# schematic.net
KiCad netlist of a schematic drawn in EAGLE
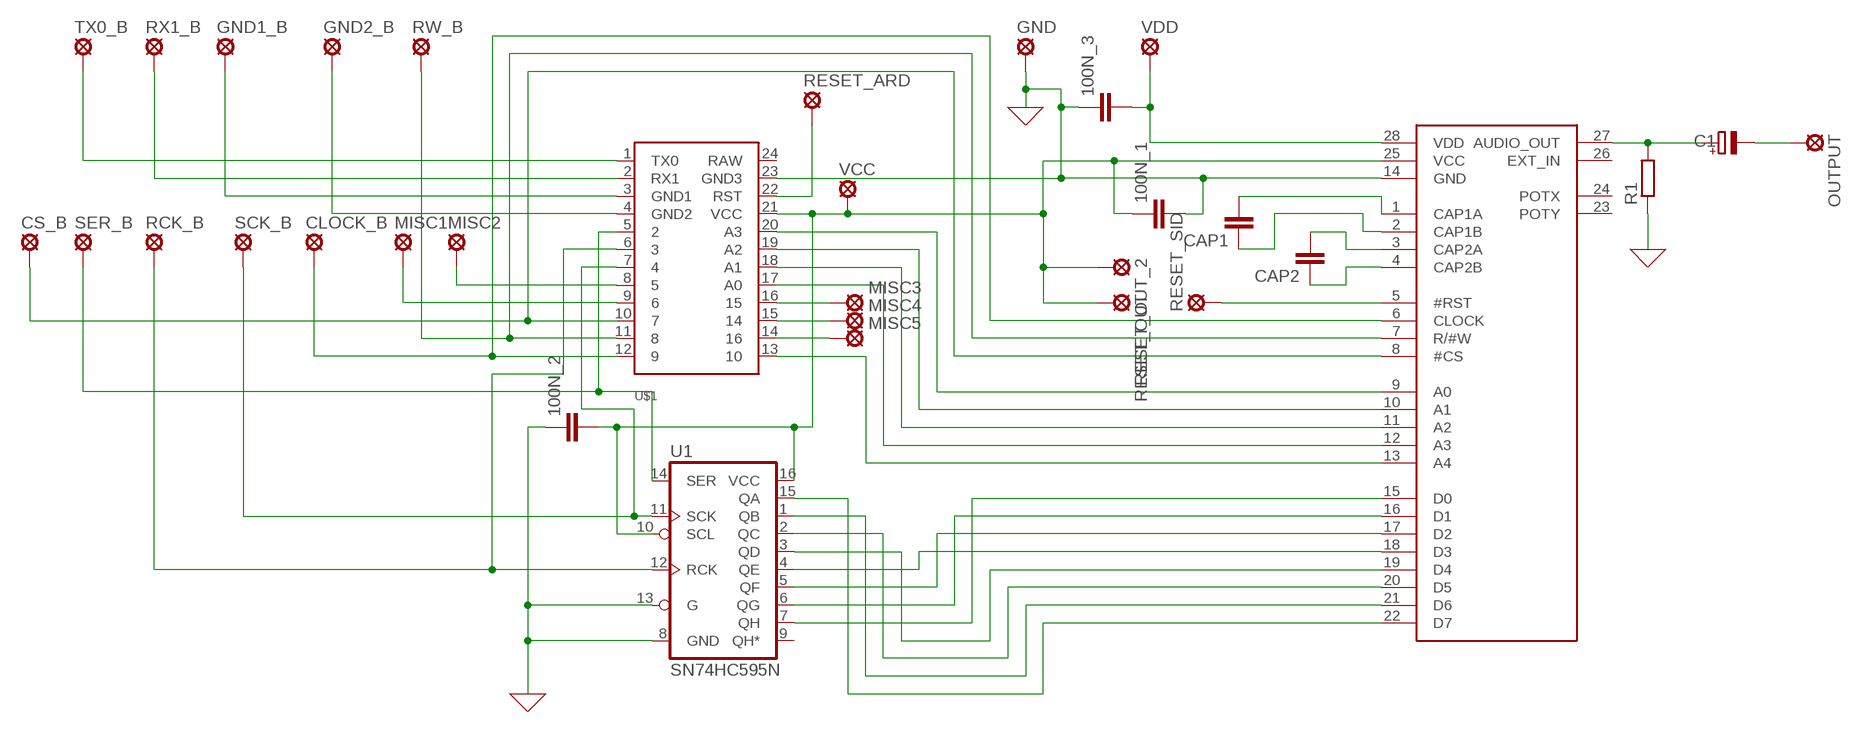
[diagram p0: schematic, sheet 1]

(export (version "E")
  (design (tool "Eeschema 10.0.6"))
  (components
    (comp (ref "100N_1")
      (value "C-EU025-025X050")
      (footprint "eagle-import:C025-025X050")
      (libsource (lib "eagle-import") (part "C-EU025-025X050"))
    )
    (comp (ref "100N_2")
      (value "C-EU050-025X075")
      (footprint "eagle-import:C050-025X075")
      (libsource (lib "eagle-import") (part "C-EU050-025X075"))
    )
    (comp (ref "100N_3")
      (value "C-EU050-025X075")
      (footprint "eagle-import:C050-025X075")
      (libsource (lib "eagle-import") (part "C-EU050-025X075"))
    )
    (comp (ref "C1")
      (value "CPOL-EUE2.5-5")
      (footprint "eagle-import:E2,5-5")
      (libsource (lib "eagle-import") (part "CPOL-EUE2.5-5"))
    )
    (comp (ref "CAP1")
      (value "C-EU050-025X075")
      (footprint "eagle-import:C050-025X075")
      (libsource (lib "eagle-import") (part "C-EU050-025X075"))
    )
    (comp (ref "CAP2")
      (value "C-EU050-025X075")
      (footprint "eagle-import:C050-025X075")
      (libsource (lib "eagle-import") (part "C-EU050-025X075"))
    )
    (comp (ref "CLOCK_B")
      (value "LSP11")
      (footprint "eagle-import:LSP11")
      (libsource (lib "eagle-import") (part "LSP11"))
    )
    (comp (ref "CS_B")
      (value "LSP11")
      (footprint "eagle-import:LSP11")
      (libsource (lib "eagle-import") (part "LSP11"))
    )
    (comp (ref "GND")
      (value "LSP11")
      (footprint "eagle-import:LSP11")
      (libsource (lib "eagle-import") (part "LSP11"))
    )
    (comp (ref "GND1_B")
      (value "LSP11")
      (footprint "eagle-import:LSP11")
      (libsource (lib "eagle-import") (part "LSP11"))
    )
    (comp (ref "GND2_B")
      (value "LSP11")
      (footprint "eagle-import:LSP11")
      (libsource (lib "eagle-import") (part "LSP11"))
    )
    (comp (ref "MISC1")
      (value "LSP11")
      (footprint "eagle-import:LSP11")
      (libsource (lib "eagle-import") (part "LSP11"))
    )
    (comp (ref "MISC2")
      (value "LSP11")
      (footprint "eagle-import:LSP11")
      (libsource (lib "eagle-import") (part "LSP11"))
    )
    (comp (ref "MISC3")
      (value "LSP11")
      (footprint "eagle-import:LSP11")
      (libsource (lib "eagle-import") (part "LSP11"))
    )
    (comp (ref "MISC4")
      (value "LSP11")
      (footprint "eagle-import:LSP11")
      (libsource (lib "eagle-import") (part "LSP11"))
    )
    (comp (ref "MISC5")
      (value "LSP11")
      (footprint "eagle-import:LSP11")
      (libsource (lib "eagle-import") (part "LSP11"))
    )
    (comp (ref "OUTPUT")
      (value "LSP11")
      (footprint "eagle-import:LSP11")
      (libsource (lib "eagle-import") (part "LSP11"))
    )
    (comp (ref "R1")
      (value "R-EU_0204/7")
      (footprint "eagle-import:0204_7")
      (libsource (lib "eagle-import") (part "R-EU_0204/7"))
    )
    (comp (ref "RCK_B")
      (value "LSP11")
      (footprint "eagle-import:LSP11")
      (libsource (lib "eagle-import") (part "LSP11"))
    )
    (comp (ref "RESET_ARD")
      (value "LSP11")
      (footprint "eagle-import:LSP11")
      (libsource (lib "eagle-import") (part "LSP11"))
    )
    (comp (ref "RESET_OUT")
      (value "LSP11")
      (footprint "eagle-import:LSP11")
      (libsource (lib "eagle-import") (part "LSP11"))
    )
    (comp (ref "RESET_OUT_2")
      (value "LSP11")
      (footprint "eagle-import:LSP11")
      (libsource (lib "eagle-import") (part "LSP11"))
    )
    (comp (ref "RESET_SID")
      (value "LSP11")
      (footprint "eagle-import:LSP11")
      (libsource (lib "eagle-import") (part "LSP11"))
    )
    (comp (ref "RW_B")
      (value "LSP11")
      (footprint "eagle-import:LSP11")
      (libsource (lib "eagle-import") (part "LSP11"))
    )
    (comp (ref "RX1_B")
      (value "LSP11")
      (footprint "eagle-import:LSP11")
      (libsource (lib "eagle-import") (part "LSP11"))
    )
    (comp (ref "SCK_B")
      (value "LSP11")
      (footprint "eagle-import:LSP11")
      (libsource (lib "eagle-import") (part "LSP11"))
    )
    (comp (ref "SER_B")
      (value "LSP11")
      (footprint "eagle-import:LSP11")
      (libsource (lib "eagle-import") (part "LSP11"))
    )
    (comp (ref "TX0_B")
      (value "LSP11")
      (footprint "eagle-import:LSP11")
      (libsource (lib "eagle-import") (part "LSP11"))
    )
    (comp (ref "U$1")
      (value "ARDUINOPROMICRO1")
      (footprint "eagle-import:PROMICRO")
      (libsource (lib "eagle-import") (part "ARDUINOPROMICRO1"))
    )
    (comp (ref "U$2")
      (value "SID_6581")
      (footprint "eagle-import:DIL28-6")
      (libsource (lib "eagle-import") (part "SID_6581"))
    )
    (comp (ref "U1")
      (value "SN74HC595N")
      (footprint "eagle-import:DIP16")
      (libsource (lib "eagle-import") (part "74595NHC"))
    )
    (comp (ref "VCC")
      (value "LSP11")
      (footprint "eagle-import:LSP11")
      (libsource (lib "eagle-import") (part "LSP11"))
    )
    (comp (ref "VDD")
      (value "LSP11")
      (footprint "eagle-import:LSP11")
      (libsource (lib "eagle-import") (part "LSP11"))
    )
  )
  (nets
    (net (code "1") (name "GND") (class "Default")
      (node (ref "100N_1") (pin "2") (pinfunction "2_2") (pintype "passive"))
      (node (ref "100N_2") (pin "1") (pinfunction "1_1") (pintype "passive"))
      (node (ref "100N_3") (pin "1") (pinfunction "1_1") (pintype "passive"))
      (node (ref "GND") (pin "MP") (pinfunction "MP_MP") (pintype "passive"))
      (node (ref "R1") (pin "1") (pinfunction "1_1") (pintype "passive"))
      (node (ref "U$1") (pin "23") (pinfunction "GND3_23") (pintype "bidirectional"))
      (node (ref "U$2") (pin "14") (pinfunction "GND_14") (pintype "bidirectional"))
      (node (ref "U1") (pin "13") (pinfunction "G_13") (pintype "input"))
      (node (ref "U1") (pin "8") (pinfunction "GND_8") (pintype "power_in"))
    )
    (net (code "2") (name "Net-(C1-Pad-)") (class "Default")
      (node (ref "C1") (pin "-") (pinfunction "-_-") (pintype "passive"))
      (node (ref "OUTPUT") (pin "MP") (pinfunction "MP_MP") (pintype "passive"))
    )
    (net (code "3") (name "Net-(U$1-2)") (class "Default")
      (node (ref "SER_B") (pin "MP") (pinfunction "MP_MP") (pintype "passive"))
      (node (ref "U$1") (pin "5") (pinfunction "2_5") (pintype "bidirectional"))
      (node (ref "U1") (pin "14") (pinfunction "SER_14") (pintype "input"))
    )
    (net (code "4") (name "Net-(U$1-3)") (class "Default")
      (node (ref "RCK_B") (pin "MP") (pinfunction "MP_MP") (pintype "passive"))
      (node (ref "U$1") (pin "6") (pinfunction "3_6") (pintype "bidirectional"))
      (node (ref "U1") (pin "12") (pinfunction "RCK_12") (pintype "input"))
    )
    (net (code "5") (name "Net-(U$1-4)") (class "Default")
      (node (ref "SCK_B") (pin "MP") (pinfunction "MP_MP") (pintype "passive"))
      (node (ref "U$1") (pin "7") (pinfunction "4_7") (pintype "bidirectional"))
      (node (ref "U1") (pin "11") (pinfunction "SCK_11") (pintype "input"))
    )
    (net (code "6") (name "Net-(U$1-5)") (class "Default")
      (node (ref "MISC2") (pin "MP") (pinfunction "MP_MP") (pintype "passive"))
      (node (ref "U$1") (pin "8") (pinfunction "5_8") (pintype "bidirectional"))
    )
    (net (code "7") (name "Net-(U$1-6)") (class "Default")
      (node (ref "MISC1") (pin "MP") (pinfunction "MP_MP") (pintype "passive"))
      (node (ref "U$1") (pin "9") (pinfunction "6_9") (pintype "bidirectional"))
    )
    (net (code "8") (name "Net-(U$1-7)") (class "Default")
      (node (ref "CS_B") (pin "MP") (pinfunction "MP_MP") (pintype "passive"))
      (node (ref "U$1") (pin "10") (pinfunction "7_10") (pintype "bidirectional"))
      (node (ref "U$2") (pin "8") (pinfunction "#CS_8") (pintype "bidirectional"))
    )
    (net (code "9") (name "Net-(U$1-8)") (class "Default")
      (node (ref "RW_B") (pin "MP") (pinfunction "MP_MP") (pintype "passive"))
      (node (ref "U$1") (pin "11") (pinfunction "8_11") (pintype "bidirectional"))
      (node (ref "U$2") (pin "7") (pinfunction "R/#W_7") (pintype "bidirectional"))
    )
    (net (code "10") (name "Net-(U$1-9)") (class "Default")
      (node (ref "CLOCK_B") (pin "MP") (pinfunction "MP_MP") (pintype "passive"))
      (node (ref "U$1") (pin "12") (pinfunction "9_12") (pintype "bidirectional"))
      (node (ref "U$2") (pin "6") (pinfunction "CLOCK_6") (pintype "bidirectional"))
    )
    (net (code "11") (name "Net-(U$1-10)") (class "Default")
      (node (ref "U$1") (pin "13") (pinfunction "10_13") (pintype "bidirectional"))
      (node (ref "U$2") (pin "13") (pinfunction "A4_13") (pintype "bidirectional"))
    )
    (net (code "12") (name "Net-(U$1-14)") (class "Default")
      (node (ref "MISC4") (pin "MP") (pinfunction "MP_MP") (pintype "passive"))
      (node (ref "U$1") (pin "15") (pinfunction "14_15") (pintype "bidirectional"))
    )
    (net (code "13") (name "Net-(U$1-15)") (class "Default")
      (node (ref "MISC3") (pin "MP") (pinfunction "MP_MP") (pintype "passive"))
      (node (ref "U$1") (pin "16") (pinfunction "15_16") (pintype "bidirectional"))
    )
    (net (code "14") (name "Net-(U$1-16)") (class "Default")
      (node (ref "MISC5") (pin "MP") (pinfunction "MP_MP") (pintype "passive"))
      (node (ref "U$1") (pin "14") (pinfunction "16_14") (pintype "bidirectional"))
    )
    (net (code "15") (name "Net-(U$1-A0)") (class "Default")
      (node (ref "U$1") (pin "17") (pinfunction "A0_17") (pintype "bidirectional"))
      (node (ref "U$2") (pin "12") (pinfunction "A3_12") (pintype "bidirectional"))
    )
    (net (code "16") (name "Net-(U$1-A1)") (class "Default")
      (node (ref "U$1") (pin "18") (pinfunction "A1_18") (pintype "bidirectional"))
      (node (ref "U$2") (pin "11") (pinfunction "A2_11") (pintype "bidirectional"))
    )
    (net (code "17") (name "Net-(U$1-A2)") (class "Default")
      (node (ref "U$1") (pin "19") (pinfunction "A2_19") (pintype "bidirectional"))
      (node (ref "U$2") (pin "10") (pinfunction "A1_10") (pintype "bidirectional"))
    )
    (net (code "18") (name "Net-(U$1-A3)") (class "Default")
      (node (ref "U$1") (pin "20") (pinfunction "A3_20") (pintype "bidirectional"))
      (node (ref "U$2") (pin "9") (pinfunction "A0_9") (pintype "bidirectional"))
    )
    (net (code "19") (name "Net-(U$1-GND1)") (class "Default")
      (node (ref "GND1_B") (pin "MP") (pinfunction "MP_MP") (pintype "passive"))
      (node (ref "U$1") (pin "3") (pinfunction "GND1_3") (pintype "bidirectional"))
    )
    (net (code "20") (name "Net-(U$1-GND2)") (class "Default")
      (node (ref "GND2_B") (pin "MP") (pinfunction "MP_MP") (pintype "passive"))
      (node (ref "U$1") (pin "4") (pinfunction "GND2_4") (pintype "bidirectional"))
    )
    (net (code "21") (name "Net-(U$1-RST)") (class "Default")
      (node (ref "RESET_ARD") (pin "MP") (pinfunction "MP_MP") (pintype "passive"))
      (node (ref "U$1") (pin "22") (pinfunction "RST_22") (pintype "bidirectional"))
    )
    (net (code "22") (name "Net-(U$1-RX1)") (class "Default")
      (node (ref "RX1_B") (pin "MP") (pinfunction "MP_MP") (pintype "passive"))
      (node (ref "U$1") (pin "2") (pinfunction "RX1_2") (pintype "bidirectional"))
    )
    (net (code "23") (name "Net-(U$1-TX0)") (class "Default")
      (node (ref "TX0_B") (pin "MP") (pinfunction "MP_MP") (pintype "passive"))
      (node (ref "U$1") (pin "1") (pinfunction "TX0_1") (pintype "bidirectional"))
    )
    (net (code "24") (name "Net-(U$1-VCC)") (class "Default")
      (node (ref "100N_1") (pin "1") (pinfunction "1_1") (pintype "passive"))
      (node (ref "100N_2") (pin "2") (pinfunction "2_2") (pintype "passive"))
      (node (ref "RESET_OUT") (pin "MP") (pinfunction "MP_MP") (pintype "passive"))
      (node (ref "RESET_OUT_2") (pin "MP") (pinfunction "MP_MP") (pintype "passive"))
      (node (ref "U$1") (pin "21") (pinfunction "VCC_21") (pintype "power_in"))
      (node (ref "U$2") (pin "25") (pinfunction "VCC_25") (pintype "bidirectional"))
      (node (ref "U1") (pin "10") (pinfunction "SCL_10") (pintype "input"))
      (node (ref "U1") (pin "16") (pinfunction "VCC_16") (pintype "power_in"))
      (node (ref "VCC") (pin "MP") (pinfunction "MP_MP") (pintype "passive"))
    )
    (net (code "25") (name "Net-(U$2-#RST)") (class "Default")
      (node (ref "RESET_SID") (pin "MP") (pinfunction "MP_MP") (pintype "passive"))
      (node (ref "U$2") (pin "5") (pinfunction "#RST_5") (pintype "bidirectional"))
    )
    (net (code "26") (name "Net-(U$2-AUDIO_OUT)") (class "Default")
      (node (ref "C1") (pin "+") (pinfunction "+_+") (pintype "passive"))
      (node (ref "R1") (pin "2") (pinfunction "2_2") (pintype "passive"))
      (node (ref "U$2") (pin "27") (pinfunction "AUDIO_OUT_27") (pintype "bidirectional"))
    )
    (net (code "27") (name "Net-(U$2-CAP1A)") (class "Default")
      (node (ref "CAP1") (pin "2") (pinfunction "2_2") (pintype "passive"))
      (node (ref "U$2") (pin "1") (pinfunction "CAP1A_1") (pintype "bidirectional"))
    )
    (net (code "28") (name "Net-(U$2-CAP1B)") (class "Default")
      (node (ref "CAP1") (pin "1") (pinfunction "1_1") (pintype "passive"))
      (node (ref "U$2") (pin "2") (pinfunction "CAP1B_2") (pintype "bidirectional"))
    )
    (net (code "29") (name "Net-(U$2-CAP2A)") (class "Default")
      (node (ref "CAP2") (pin "2") (pinfunction "2_2") (pintype "passive"))
      (node (ref "U$2") (pin "3") (pinfunction "CAP2A_3") (pintype "bidirectional"))
    )
    (net (code "30") (name "Net-(U$2-CAP2B)") (class "Default")
      (node (ref "CAP2") (pin "1") (pinfunction "1_1") (pintype "passive"))
      (node (ref "U$2") (pin "4") (pinfunction "CAP2B_4") (pintype "bidirectional"))
    )
    (net (code "31") (name "Net-(U$2-D0)") (class "Default")
      (node (ref "U$2") (pin "15") (pinfunction "D0_15") (pintype "bidirectional"))
      (node (ref "U1") (pin "7") (pinfunction "QH_7") (pintype "tri_state"))
    )
    (net (code "32") (name "Net-(U$2-D1)") (class "Default")
      (node (ref "U$2") (pin "16") (pinfunction "D1_16") (pintype "bidirectional"))
      (node (ref "U1") (pin "6") (pinfunction "QG_6") (pintype "tri_state"))
    )
    (net (code "33") (name "Net-(U$2-D2)") (class "Default")
      (node (ref "U$2") (pin "17") (pinfunction "D2_17") (pintype "bidirectional"))
      (node (ref "U1") (pin "5") (pinfunction "QF_5") (pintype "tri_state"))
    )
    (net (code "34") (name "Net-(U$2-D3)") (class "Default")
      (node (ref "U$2") (pin "18") (pinfunction "D3_18") (pintype "bidirectional"))
      (node (ref "U1") (pin "4") (pinfunction "QE_4") (pintype "tri_state"))
    )
    (net (code "35") (name "Net-(U$2-D4)") (class "Default")
      (node (ref "U$2") (pin "19") (pinfunction "D4_19") (pintype "bidirectional"))
      (node (ref "U1") (pin "3") (pinfunction "QD_3") (pintype "tri_state"))
    )
    (net (code "36") (name "Net-(U$2-D5)") (class "Default")
      (node (ref "U$2") (pin "20") (pinfunction "D5_20") (pintype "bidirectional"))
      (node (ref "U1") (pin "2") (pinfunction "QC_2") (pintype "tri_state"))
    )
    (net (code "37") (name "Net-(U$2-D6)") (class "Default")
      (node (ref "U$2") (pin "21") (pinfunction "D6_21") (pintype "bidirectional"))
      (node (ref "U1") (pin "1") (pinfunction "QB_1") (pintype "tri_state"))
    )
    (net (code "38") (name "Net-(U$2-D7)") (class "Default")
      (node (ref "U$2") (pin "22") (pinfunction "D7_22") (pintype "bidirectional"))
      (node (ref "U1") (pin "15") (pinfunction "QA_15") (pintype "tri_state"))
    )
    (net (code "39") (name "Net-(U$2-VDD)") (class "Default")
      (node (ref "100N_3") (pin "2") (pinfunction "2_2") (pintype "passive"))
      (node (ref "U$2") (pin "28") (pinfunction "VDD_28") (pintype "bidirectional"))
      (node (ref "VDD") (pin "MP") (pinfunction "MP_MP") (pintype "passive"))
    )
    (net (code "40") (name "unconnected-(U$1-RAW-Pad24)") (class "Default")
      (node (ref "U$1") (pin "24") (pinfunction "RAW_24") (pintype "bidirectional"))
    )
    (net (code "41") (name "unconnected-(U$2-EXT_IN-Pad26)") (class "Default")
      (node (ref "U$2") (pin "26") (pinfunction "EXT_IN_26") (pintype "bidirectional"))
    )
    (net (code "42") (name "unconnected-(U$2-POTX-Pad24)") (class "Default")
      (node (ref "U$2") (pin "24") (pinfunction "POTX_24") (pintype "bidirectional"))
    )
    (net (code "43") (name "unconnected-(U$2-POTY-Pad23)") (class "Default")
      (node (ref "U$2") (pin "23") (pinfunction "POTY_23") (pintype "bidirectional"))
    )
    (net (code "44") (name "unconnected-(U1-QH*-Pad9)") (class "Default")
      (node (ref "U1") (pin "9") (pinfunction "QH*_9") (pintype "tri_state"))
    )
  )
)
